# v3_bpard.net
KiCad netlist of a schematic drawn in EAGLE
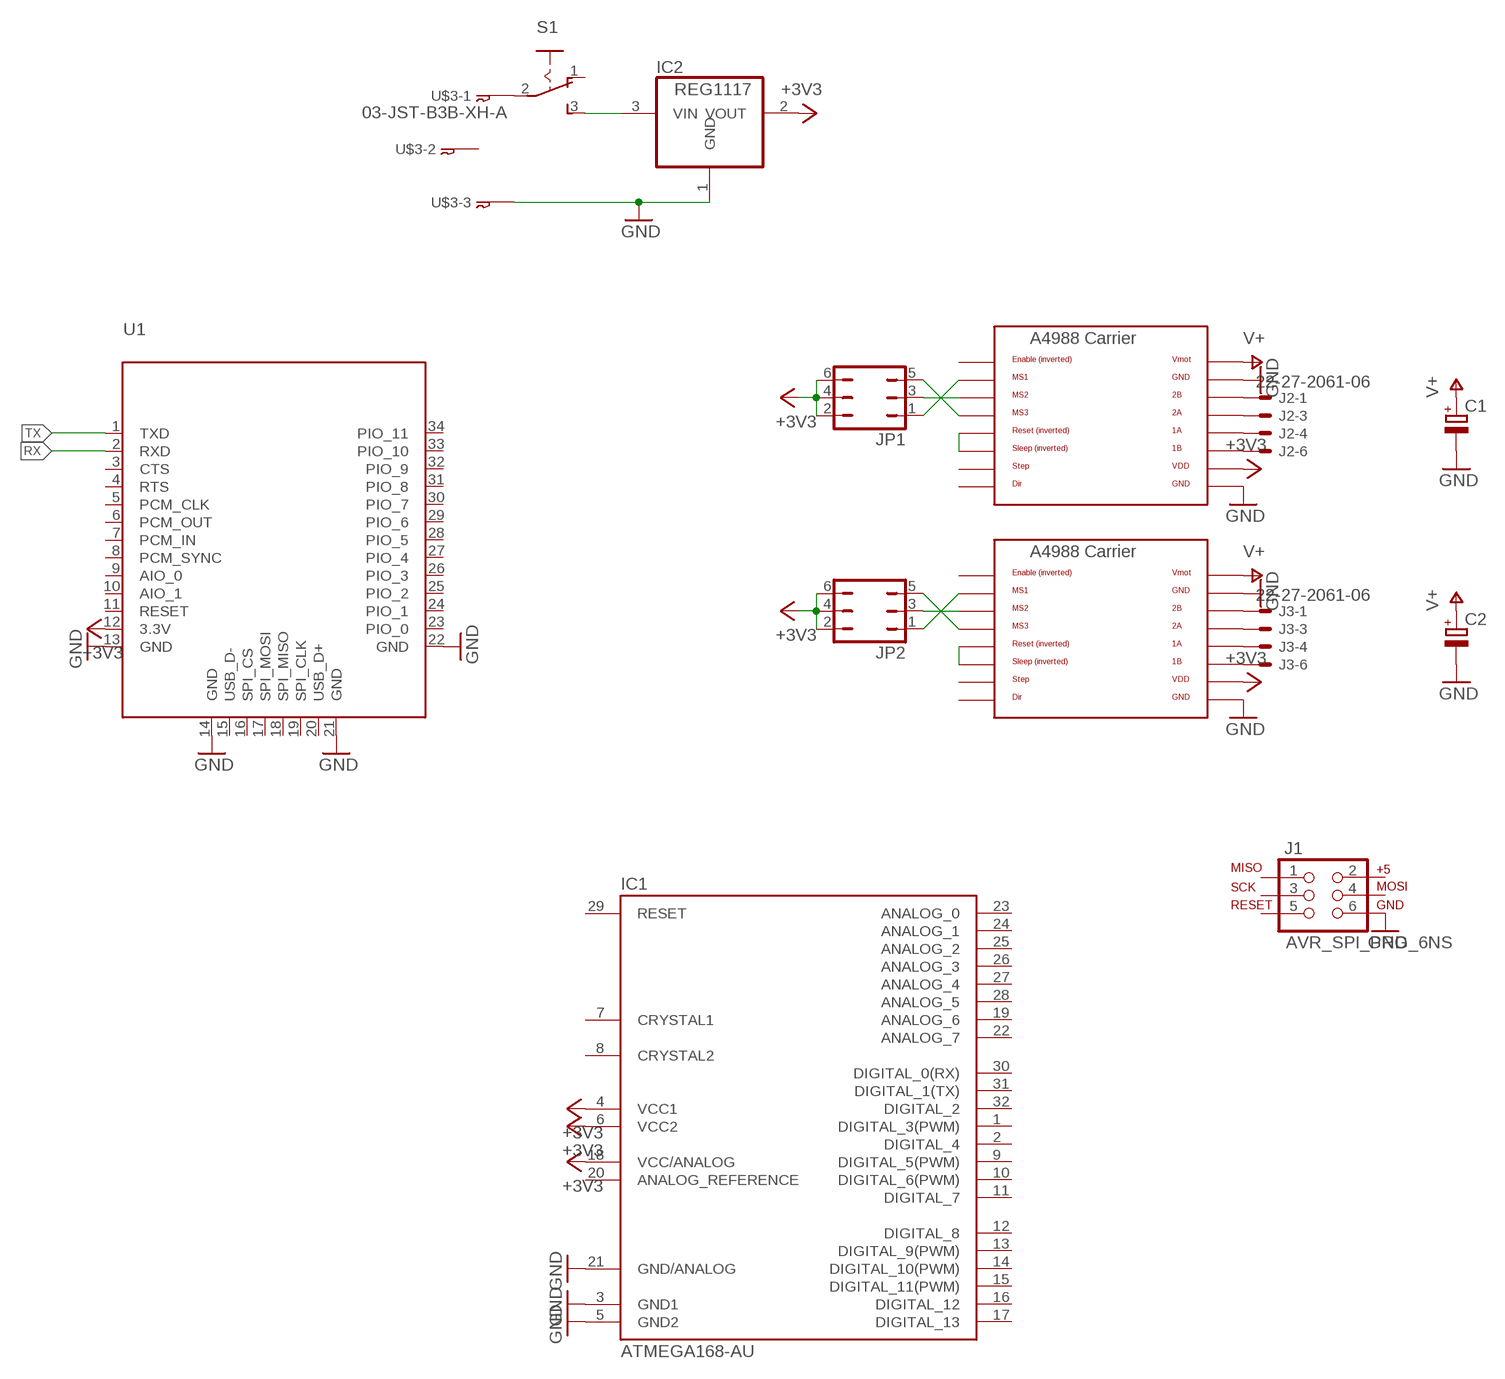
[diagram p0: schematic, sheet 1]

(export (version "E")
  (design (tool "Eeschema 10.0.6"))
  (components
    (comp (ref "C1")
      (value "CPOL-EUE5-8.5")
      (footprint "eagle-import:E5-8,5")
      (libsource (lib "eagle-import") (part "CPOL-EUE5-8.5"))
    )
    (comp (ref "C2")
      (value "CPOL-EUE5-8.5")
      (footprint "eagle-import:E5-8,5")
      (libsource (lib "eagle-import") (part "CPOL-EUE5-8.5"))
    )
    (comp (ref "IC1")
      (value "ATMEGA168-AU")
      (footprint "eagle-import:TQFP32-08")
      (libsource (lib "eagle-import") (part "ATMEGA168-AU"))
    )
    (comp (ref "IC2")
      (value "REG1117")
      (footprint "eagle-import:SOT223")
      (libsource (lib "eagle-import") (part "REG1117"))
    )
    (comp (ref "J1")
      (value "AVR_SPI_PRG_6NS")
      (footprint "eagle-import:2X3-NS")
      (libsource (lib "eagle-import") (part "AVR_SPI_PRG_6NS"))
    )
    (comp (ref "J2")
      (value "22-27-2061-06")
      (footprint "eagle-import:6410-06")
      (libsource (lib "eagle-import") (part "22-?-0627-2061"))
    )
    (comp (ref "J3")
      (value "22-27-2061-06")
      (footprint "eagle-import:6410-06")
      (libsource (lib "eagle-import") (part "22-?-0627-2061"))
    )
    (comp (ref "JP1")
      (value "JP3Q")
      (footprint "eagle-import:JP3Q")
      (libsource (lib "eagle-import") (part "JP3Q"))
    )
    (comp (ref "JP2")
      (value "JP3Q")
      (footprint "eagle-import:JP3Q")
      (libsource (lib "eagle-import") (part "JP3Q"))
    )
    (comp (ref "S1")
      (value "255SB")
      (footprint "eagle-import:255SB")
      (libsource (lib "eagle-import") (part "255SB"))
    )
    (comp (ref "U$1")
      (value "POLOLU_A4983CARRIER")
      (footprint "eagle-import:A4988BREAKOUT")
      (libsource (lib "eagle-import") (part "POLOLU_A4983CARRIER"))
    )
    (comp (ref "U$2")
      (value "POLOLU_A4983CARRIER")
      (footprint "eagle-import:A4988BREAKOUT")
      (libsource (lib "eagle-import") (part "POLOLU_A4983CARRIER"))
    )
    (comp (ref "U$3")
      (value "03-JST-B3B-XH-A")
      (footprint "eagle-import:B3B-XH")
      (libsource (lib "eagle-import") (part "03-JST-B3B-XH-A"))
    )
    (comp (ref "U1")
      (value "BLUETOOTH_MODULE")
      (footprint "eagle-import:BLUETOOTH_MODULE")
      (libsource (lib "eagle-import") (part "BLUETOOTH_MODULE"))
    )
  )
  (nets
    (net (code "1") (name "+3V3") (class "Default")
      (node (ref "IC1") (pin "18") (pinfunction "VCC/ANALOG_18") (pintype "passive"))
      (node (ref "IC1") (pin "4") (pinfunction "VCC1_4") (pintype "power_in"))
      (node (ref "IC1") (pin "6") (pinfunction "VCC2_6") (pintype "power_in"))
      (node (ref "IC2") (pin "2") (pinfunction "VOUT_2") (pintype "output"))
      (node (ref "JP1") (pin "2") (pinfunction "2_2") (pintype "passive"))
      (node (ref "JP1") (pin "4") (pinfunction "4_4") (pintype "passive"))
      (node (ref "JP1") (pin "6") (pinfunction "6_6") (pintype "passive"))
      (node (ref "JP2") (pin "2") (pinfunction "2_2") (pintype "passive"))
      (node (ref "JP2") (pin "4") (pinfunction "4_4") (pintype "passive"))
      (node (ref "JP2") (pin "6") (pinfunction "6_6") (pintype "passive"))
      (node (ref "U$1") (pin "VDD") (pinfunction "VDD_VDD") (pintype "power_in"))
      (node (ref "U$2") (pin "VDD") (pinfunction "VDD_VDD") (pintype "power_in"))
      (node (ref "U1") (pin "12") (pinfunction "3.3V_12") (pintype "power_in"))
    )
    (net (code "2") (name "GND") (class "Default")
      (node (ref "C1") (pin "-") (pinfunction "-_-") (pintype "passive"))
      (node (ref "C2") (pin "-") (pinfunction "-_-") (pintype "passive"))
      (node (ref "IC1") (pin "21") (pinfunction "GND/ANALOG_21") (pintype "power_in"))
      (node (ref "IC1") (pin "3") (pinfunction "GND1_3") (pintype "power_in"))
      (node (ref "IC1") (pin "5") (pinfunction "GND2_5") (pintype "power_in"))
      (node (ref "IC2") (pin "1") (pinfunction "GND_1") (pintype "power_in"))
      (node (ref "J1") (pin "6") (pinfunction "6_6") (pintype "passive"))
      (node (ref "U$1") (pin "GND") (pinfunction "GND_GND") (pintype "power_in"))
      (node (ref "U$1") (pin "GND@0") (pinfunction "GND_GND@0") (pintype "power_in"))
      (node (ref "U$2") (pin "GND") (pinfunction "GND_GND") (pintype "power_in"))
      (node (ref "U$2") (pin "GND@0") (pinfunction "GND_GND@0") (pintype "power_in"))
      (node (ref "U$3") (pin "P$3") (pinfunction "1_P$3") (pintype "passive"))
      (node (ref "U1") (pin "13") (pinfunction "GND_13") (pintype "power_in"))
      (node (ref "U1") (pin "14") (pinfunction "GND_14") (pintype "power_in"))
      (node (ref "U1") (pin "21") (pinfunction "GND_21") (pintype "power_in"))
      (node (ref "U1") (pin "22") (pinfunction "GND_22") (pintype "power_in"))
    )
    (net (code "3") (name "Net-(J2A-S)") (class "Default")
      (node (ref "J2") (pin "1") (pinfunction "S_1") (pintype "passive"))
      (node (ref "U$1") (pin "2B") (pinfunction "2B_2B") (pintype "output"))
    )
    (net (code "4") (name "Net-(J2C-S)") (class "Default")
      (node (ref "J2") (pin "3") (pinfunction "S_3") (pintype "passive"))
      (node (ref "U$1") (pin "2A") (pinfunction "2A_2A") (pintype "output"))
    )
    (net (code "5") (name "Net-(J2D-S)") (class "Default")
      (node (ref "J2") (pin "4") (pinfunction "S_4") (pintype "passive"))
      (node (ref "U$1") (pin "1A") (pinfunction "1A_1A") (pintype "output"))
    )
    (net (code "6") (name "Net-(J2F-S)") (class "Default")
      (node (ref "J2") (pin "6") (pinfunction "S_6") (pintype "passive"))
      (node (ref "U$1") (pin "1B") (pinfunction "1B_1B") (pintype "output"))
    )
    (net (code "7") (name "Net-(J3A-S)") (class "Default")
      (node (ref "J3") (pin "1") (pinfunction "S_1") (pintype "passive"))
      (node (ref "U$2") (pin "2B") (pinfunction "2B_2B") (pintype "output"))
    )
    (net (code "8") (name "Net-(J3C-S)") (class "Default")
      (node (ref "J3") (pin "3") (pinfunction "S_3") (pintype "passive"))
      (node (ref "U$2") (pin "2A") (pinfunction "2A_2A") (pintype "output"))
    )
    (net (code "9") (name "Net-(J3D-S)") (class "Default")
      (node (ref "J3") (pin "4") (pinfunction "S_4") (pintype "passive"))
      (node (ref "U$2") (pin "1A") (pinfunction "1A_1A") (pintype "output"))
    )
    (net (code "10") (name "Net-(J3F-S)") (class "Default")
      (node (ref "J3") (pin "6") (pinfunction "S_6") (pintype "passive"))
      (node (ref "U$2") (pin "1B") (pinfunction "1B_1B") (pintype "output"))
    )
    (net (code "11") (name "Net-(JP1-Pad1)") (class "Default")
      (node (ref "JP1") (pin "1") (pinfunction "1_1") (pintype "passive"))
      (node (ref "U$1") (pin "MS1") (pinfunction "MS1_MS1") (pintype "input"))
    )
    (net (code "12") (name "Net-(JP1-Pad3)") (class "Default")
      (node (ref "JP1") (pin "3") (pinfunction "3_3") (pintype "passive"))
      (node (ref "U$1") (pin "MS2") (pinfunction "MS2_MS2") (pintype "input"))
    )
    (net (code "13") (name "Net-(JP1-Pad5)") (class "Default")
      (node (ref "JP1") (pin "5") (pinfunction "5_5") (pintype "passive"))
      (node (ref "U$1") (pin "MS3") (pinfunction "MS3_MS3") (pintype "input"))
    )
    (net (code "14") (name "Net-(JP2-Pad1)") (class "Default")
      (node (ref "JP2") (pin "1") (pinfunction "1_1") (pintype "passive"))
      (node (ref "U$2") (pin "MS1") (pinfunction "MS1_MS1") (pintype "input"))
    )
    (net (code "15") (name "Net-(JP2-Pad3)") (class "Default")
      (node (ref "JP2") (pin "3") (pinfunction "3_3") (pintype "passive"))
      (node (ref "U$2") (pin "MS2") (pinfunction "MS2_MS2") (pintype "input"))
    )
    (net (code "16") (name "Net-(JP2-Pad5)") (class "Default")
      (node (ref "JP2") (pin "5") (pinfunction "5_5") (pintype "passive"))
      (node (ref "U$2") (pin "MS3") (pinfunction "MS3_MS3") (pintype "input"))
    )
    (net (code "17") (name "Net-(S1-P)") (class "Default")
      (node (ref "S1") (pin "2") (pinfunction "P_2") (pintype "passive"))
      (node (ref "U$3") (pin "P$1") (pinfunction "1_P$1") (pintype "passive"))
    )
    (net (code "18") (name "Net-(U$1-SLEEP)") (class "Default")
      (node (ref "U$1") (pin "RST") (pinfunction "RST_RST") (pintype "input"))
      (node (ref "U$1") (pin "SLP") (pinfunction "SLEEP_SLP") (pintype "input"))
    )
    (net (code "19") (name "Net-(U$2-SLEEP)") (class "Default")
      (node (ref "U$2") (pin "RST") (pinfunction "RST_RST") (pintype "input"))
      (node (ref "U$2") (pin "SLP") (pinfunction "SLEEP_SLP") (pintype "input"))
    )
    (net (code "20") (name "RX") (class "Default")
      (node (ref "U1") (pin "2") (pinfunction "RXD_2") (pintype "bidirectional"))
    )
    (net (code "21") (name "TX") (class "Default")
      (node (ref "U1") (pin "1") (pinfunction "TXD_1") (pintype "bidirectional"))
    )
    (net (code "22") (name "V+") (class "Default")
      (node (ref "C1") (pin "+") (pinfunction "+_+") (pintype "passive"))
      (node (ref "C2") (pin "+") (pinfunction "+_+") (pintype "passive"))
      (node (ref "IC2") (pin "3") (pinfunction "VIN_3") (pintype "input"))
      (node (ref "S1") (pin "3") (pinfunction "S_3") (pintype "passive"))
      (node (ref "U$1") (pin "VMOT") (pinfunction "VMOT_VMOT") (pintype "power_in"))
      (node (ref "U$2") (pin "VMOT") (pinfunction "VMOT_VMOT") (pintype "power_in"))
    )
    (net (code "23") (name "unconnected-(IC1-ANALOG_0-Pad23)") (class "Default")
      (node (ref "IC1") (pin "23") (pinfunction "ANALOG_0_23") (pintype "bidirectional"))
    )
    (net (code "24") (name "unconnected-(IC1-ANALOG_1-Pad24)") (class "Default")
      (node (ref "IC1") (pin "24") (pinfunction "ANALOG_1_24") (pintype "bidirectional"))
    )
    (net (code "25") (name "unconnected-(IC1-ANALOG_2-Pad25)") (class "Default")
      (node (ref "IC1") (pin "25") (pinfunction "ANALOG_2_25") (pintype "bidirectional"))
    )
    (net (code "26") (name "unconnected-(IC1-ANALOG_3-Pad26)") (class "Default")
      (node (ref "IC1") (pin "26") (pinfunction "ANALOG_3_26") (pintype "bidirectional"))
    )
    (net (code "27") (name "unconnected-(IC1-ANALOG_4-Pad27)") (class "Default")
      (node (ref "IC1") (pin "27") (pinfunction "ANALOG_4_27") (pintype "bidirectional"))
    )
    (net (code "28") (name "unconnected-(IC1-ANALOG_5-Pad28)") (class "Default")
      (node (ref "IC1") (pin "28") (pinfunction "ANALOG_5_28") (pintype "bidirectional"))
    )
    (net (code "29") (name "unconnected-(IC1-ANALOG_6-Pad19)") (class "Default")
      (node (ref "IC1") (pin "19") (pinfunction "ANALOG_6_19") (pintype "passive"))
    )
    (net (code "30") (name "unconnected-(IC1-ANALOG_7-Pad22)") (class "Default")
      (node (ref "IC1") (pin "22") (pinfunction "ANALOG_7_22") (pintype "passive"))
    )
    (net (code "31") (name "unconnected-(IC1-ANALOG_REFERENCE-Pad20)") (class "Default")
      (node (ref "IC1") (pin "20") (pinfunction "ANALOG_REFERENCE_20") (pintype "passive"))
    )
    (net (code "32") (name "unconnected-(IC1-CRYSTAL1-Pad7)") (class "Default")
      (node (ref "IC1") (pin "7") (pinfunction "CRYSTAL1_7") (pintype "bidirectional"))
    )
    (net (code "33") (name "unconnected-(IC1-CRYSTAL2-Pad8)") (class "Default")
      (node (ref "IC1") (pin "8") (pinfunction "CRYSTAL2_8") (pintype "bidirectional"))
    )
    (net (code "34") (name "unconnected-(IC1-DIGITAL_0(RX)-Pad30)") (class "Default")
      (node (ref "IC1") (pin "30") (pinfunction "DIGITAL_0(RX)_30") (pintype "bidirectional"))
    )
    (net (code "35") (name "unconnected-(IC1-DIGITAL_1(TX)-Pad31)") (class "Default")
      (node (ref "IC1") (pin "31") (pinfunction "DIGITAL_1(TX)_31") (pintype "bidirectional"))
    )
    (net (code "36") (name "unconnected-(IC1-DIGITAL_2-Pad32)") (class "Default")
      (node (ref "IC1") (pin "32") (pinfunction "DIGITAL_2_32") (pintype "bidirectional"))
    )
    (net (code "37") (name "unconnected-(IC1-DIGITAL_3(PWM)-Pad1)") (class "Default")
      (node (ref "IC1") (pin "1") (pinfunction "DIGITAL_3(PWM)_1") (pintype "bidirectional"))
    )
    (net (code "38") (name "unconnected-(IC1-DIGITAL_4-Pad2)") (class "Default")
      (node (ref "IC1") (pin "2") (pinfunction "DIGITAL_4_2") (pintype "bidirectional"))
    )
    (net (code "39") (name "unconnected-(IC1-DIGITAL_5(PWM)-Pad9)") (class "Default")
      (node (ref "IC1") (pin "9") (pinfunction "DIGITAL_5(PWM)_9") (pintype "bidirectional"))
    )
    (net (code "40") (name "unconnected-(IC1-DIGITAL_6(PWM)-Pad10)") (class "Default")
      (node (ref "IC1") (pin "10") (pinfunction "DIGITAL_6(PWM)_10") (pintype "bidirectional"))
    )
    (net (code "41") (name "unconnected-(IC1-DIGITAL_7-Pad11)") (class "Default")
      (node (ref "IC1") (pin "11") (pinfunction "DIGITAL_7_11") (pintype "bidirectional"))
    )
    (net (code "42") (name "unconnected-(IC1-DIGITAL_8-Pad12)") (class "Default")
      (node (ref "IC1") (pin "12") (pinfunction "DIGITAL_8_12") (pintype "bidirectional"))
    )
    (net (code "43") (name "unconnected-(IC1-DIGITAL_9(PWM)-Pad13)") (class "Default")
      (node (ref "IC1") (pin "13") (pinfunction "DIGITAL_9(PWM)_13") (pintype "bidirectional"))
    )
    (net (code "44") (name "unconnected-(IC1-DIGITAL_10(PWM)-Pad14)") (class "Default")
      (node (ref "IC1") (pin "14") (pinfunction "DIGITAL_10(PWM)_14") (pintype "bidirectional"))
    )
    (net (code "45") (name "unconnected-(IC1-DIGITAL_11(PWM)-Pad15)") (class "Default")
      (node (ref "IC1") (pin "15") (pinfunction "DIGITAL_11(PWM)_15") (pintype "bidirectional"))
    )
    (net (code "46") (name "unconnected-(IC1-DIGITAL_12-Pad16)") (class "Default")
      (node (ref "IC1") (pin "16") (pinfunction "DIGITAL_12_16") (pintype "bidirectional"))
    )
    (net (code "47") (name "unconnected-(IC1-DIGITAL_13-Pad17)") (class "Default")
      (node (ref "IC1") (pin "17") (pinfunction "DIGITAL_13_17") (pintype "bidirectional"))
    )
    (net (code "48") (name "unconnected-(IC1-RESET-Pad29)") (class "Default")
      (node (ref "IC1") (pin "29") (pinfunction "RESET_29") (pintype "bidirectional"))
    )
    (net (code "49") (name "unconnected-(J1-Pad1)") (class "Default")
      (node (ref "J1") (pin "1") (pinfunction "1_1") (pintype "passive"))
    )
    (net (code "50") (name "unconnected-(J1-Pad2)") (class "Default")
      (node (ref "J1") (pin "2") (pinfunction "2_2") (pintype "passive"))
    )
    (net (code "51") (name "unconnected-(J1-Pad3)") (class "Default")
      (node (ref "J1") (pin "3") (pinfunction "3_3") (pintype "passive"))
    )
    (net (code "52") (name "unconnected-(J1-Pad4)") (class "Default")
      (node (ref "J1") (pin "4") (pinfunction "4_4") (pintype "passive"))
    )
    (net (code "53") (name "unconnected-(J1-Pad5)") (class "Default")
      (node (ref "J1") (pin "5") (pinfunction "5_5") (pintype "passive"))
    )
    (net (code "54") (name "unconnected-(S1-O-Pad1)") (class "Default")
      (node (ref "S1") (pin "1") (pinfunction "O_1") (pintype "passive"))
    )
    (net (code "55") (name "unconnected-(U$1-PadDIR)") (class "Default")
      (node (ref "U$1") (pin "DIR") (pinfunction "DIR_DIR") (pintype "input"))
    )
    (net (code "56") (name "unconnected-(U$1-PadEN)") (class "Default")
      (node (ref "U$1") (pin "EN") (pinfunction "EN_EN") (pintype "input"))
    )
    (net (code "57") (name "unconnected-(U$1-PadSTEP)") (class "Default")
      (node (ref "U$1") (pin "STEP") (pinfunction "STEP_STEP") (pintype "input"))
    )
    (net (code "58") (name "unconnected-(U$2-PadDIR)") (class "Default")
      (node (ref "U$2") (pin "DIR") (pinfunction "DIR_DIR") (pintype "input"))
    )
    (net (code "59") (name "unconnected-(U$2-PadEN)") (class "Default")
      (node (ref "U$2") (pin "EN") (pinfunction "EN_EN") (pintype "input"))
    )
    (net (code "60") (name "unconnected-(U$2-PadSTEP)") (class "Default")
      (node (ref "U$2") (pin "STEP") (pinfunction "STEP_STEP") (pintype "input"))
    )
    (net (code "61") (name "unconnected-(U$3B-1-PadP$2)") (class "Default")
      (node (ref "U$3") (pin "P$2") (pinfunction "1_P$2") (pintype "passive"))
    )
    (net (code "62") (name "unconnected-(U1-AIO_0-Pad9)") (class "Default")
      (node (ref "U1") (pin "9") (pinfunction "AIO_0_9") (pintype "bidirectional"))
    )
    (net (code "63") (name "unconnected-(U1-AIO_1-Pad10)") (class "Default")
      (node (ref "U1") (pin "10") (pinfunction "AIO_1_10") (pintype "bidirectional"))
    )
    (net (code "64") (name "unconnected-(U1-CTS-Pad3)") (class "Default")
      (node (ref "U1") (pin "3") (pinfunction "CTS_3") (pintype "bidirectional"))
    )
    (net (code "65") (name "unconnected-(U1-PCM_CLK-Pad5)") (class "Default")
      (node (ref "U1") (pin "5") (pinfunction "PCM_CLK_5") (pintype "bidirectional"))
    )
    (net (code "66") (name "unconnected-(U1-PCM_IN-Pad7)") (class "Default")
      (node (ref "U1") (pin "7") (pinfunction "PCM_IN_7") (pintype "bidirectional"))
    )
    (net (code "67") (name "unconnected-(U1-PCM_OUT-Pad6)") (class "Default")
      (node (ref "U1") (pin "6") (pinfunction "PCM_OUT_6") (pintype "bidirectional"))
    )
    (net (code "68") (name "unconnected-(U1-PCM_SYNC-Pad8)") (class "Default")
      (node (ref "U1") (pin "8") (pinfunction "PCM_SYNC_8") (pintype "bidirectional"))
    )
    (net (code "69") (name "unconnected-(U1-PIO_0-Pad23)") (class "Default")
      (node (ref "U1") (pin "23") (pinfunction "PIO_0_23") (pintype "bidirectional"))
    )
    (net (code "70") (name "unconnected-(U1-PIO_1-Pad24)") (class "Default")
      (node (ref "U1") (pin "24") (pinfunction "PIO_1_24") (pintype "bidirectional"))
    )
    (net (code "71") (name "unconnected-(U1-PIO_2-Pad25)") (class "Default")
      (node (ref "U1") (pin "25") (pinfunction "PIO_2_25") (pintype "bidirectional"))
    )
    (net (code "72") (name "unconnected-(U1-PIO_3-Pad26)") (class "Default")
      (node (ref "U1") (pin "26") (pinfunction "PIO_3_26") (pintype "bidirectional"))
    )
    (net (code "73") (name "unconnected-(U1-PIO_4-Pad27)") (class "Default")
      (node (ref "U1") (pin "27") (pinfunction "PIO_4_27") (pintype "bidirectional"))
    )
    (net (code "74") (name "unconnected-(U1-PIO_5-Pad28)") (class "Default")
      (node (ref "U1") (pin "28") (pinfunction "PIO_5_28") (pintype "bidirectional"))
    )
    (net (code "75") (name "unconnected-(U1-PIO_6-Pad29)") (class "Default")
      (node (ref "U1") (pin "29") (pinfunction "PIO_6_29") (pintype "bidirectional"))
    )
    (net (code "76") (name "unconnected-(U1-PIO_7-Pad30)") (class "Default")
      (node (ref "U1") (pin "30") (pinfunction "PIO_7_30") (pintype "bidirectional"))
    )
    (net (code "77") (name "unconnected-(U1-PIO_8-Pad31)") (class "Default")
      (node (ref "U1") (pin "31") (pinfunction "PIO_8_31") (pintype "bidirectional"))
    )
    (net (code "78") (name "unconnected-(U1-PIO_9-Pad32)") (class "Default")
      (node (ref "U1") (pin "32") (pinfunction "PIO_9_32") (pintype "bidirectional"))
    )
    (net (code "79") (name "unconnected-(U1-PIO_10-Pad33)") (class "Default")
      (node (ref "U1") (pin "33") (pinfunction "PIO_10_33") (pintype "bidirectional"))
    )
    (net (code "80") (name "unconnected-(U1-PIO_11-Pad34)") (class "Default")
      (node (ref "U1") (pin "34") (pinfunction "PIO_11_34") (pintype "bidirectional"))
    )
    (net (code "81") (name "unconnected-(U1-RESET-Pad11)") (class "Default")
      (node (ref "U1") (pin "11") (pinfunction "RESET_11") (pintype "bidirectional"))
    )
    (net (code "82") (name "unconnected-(U1-RTS-Pad4)") (class "Default")
      (node (ref "U1") (pin "4") (pinfunction "RTS_4") (pintype "bidirectional"))
    )
    (net (code "83") (name "unconnected-(U1-SPI_CLK-Pad19)") (class "Default")
      (node (ref "U1") (pin "19") (pinfunction "SPI_CLK_19") (pintype "bidirectional"))
    )
    (net (code "84") (name "unconnected-(U1-SPI_CS-Pad16)") (class "Default")
      (node (ref "U1") (pin "16") (pinfunction "SPI_CS_16") (pintype "bidirectional"))
    )
    (net (code "85") (name "unconnected-(U1-SPI_MISO-Pad18)") (class "Default")
      (node (ref "U1") (pin "18") (pinfunction "SPI_MISO_18") (pintype "bidirectional"))
    )
    (net (code "86") (name "unconnected-(U1-SPI_MOSI-Pad17)") (class "Default")
      (node (ref "U1") (pin "17") (pinfunction "SPI_MOSI_17") (pintype "bidirectional"))
    )
    (net (code "87") (name "unconnected-(U1-USB_D+-Pad20)") (class "Default")
      (node (ref "U1") (pin "20") (pinfunction "USB_D+_20") (pintype "bidirectional"))
    )
    (net (code "88") (name "unconnected-(U1-USB_D--Pad15)") (class "Default")
      (node (ref "U1") (pin "15") (pinfunction "USB_D-_15") (pintype "bidirectional"))
    )
  )
)
